# PCIe_x4.net
KiCad netlist of a schematic drawn in Altium Designer
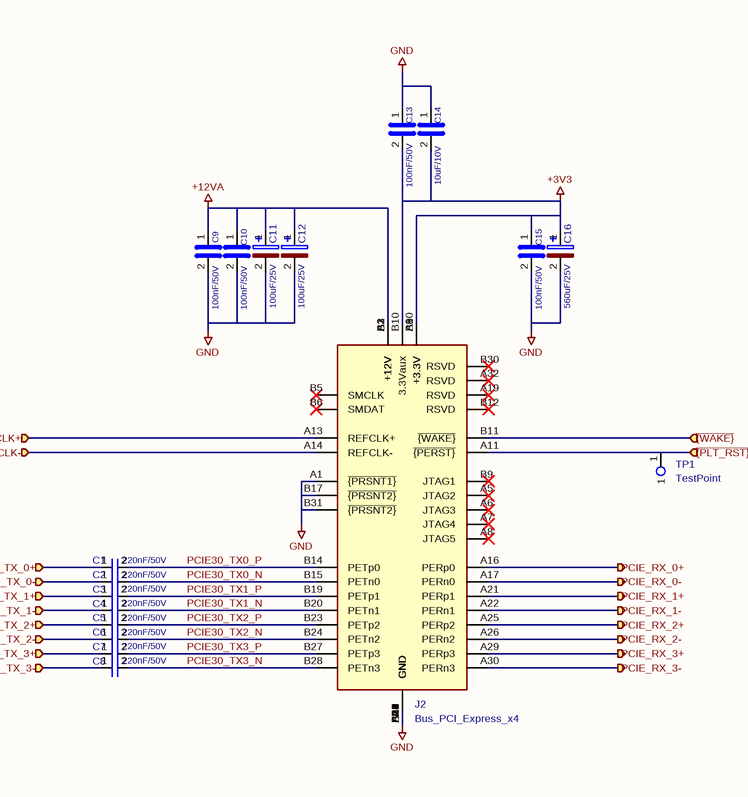
[diagram p0: PCIe x4.SchDoc]

(export (version "E")
  (design (tool "Eeschema 10.0.6"))
  (components
    (comp (ref "C1") (value "220nF/50V") (libsource (lib "Device") (part "C_Small")))
    (comp (ref "C2") (value "220nF/50V") (libsource (lib "Device") (part "C_Small")))
    (comp (ref "C3") (value "220nF/50V") (libsource (lib "Device") (part "C_Small")))
    (comp (ref "C4") (value "220nF/50V") (libsource (lib "Device") (part "C_Small")))
    (comp (ref "C5") (value "220nF/50V") (libsource (lib "Device") (part "C_Small")))
    (comp (ref "C6") (value "220nF/50V") (libsource (lib "Device") (part "C_Small")))
    (comp (ref "C7") (value "220nF/50V") (libsource (lib "Device") (part "C_Small")))
    (comp (ref "C8") (value "220nF/50V") (libsource (lib "Device") (part "C_Small")))
    (comp (ref "C9") (value "100nF/50V") (libsource (lib "Device") (part "C")))
    (comp (ref "C10") (value "100nF/50V") (libsource (lib "Device") (part "C")))
    (comp (ref "C11") (value "100uF/25V") (libsource (lib "Device") (part "C_Polarized")))
    (comp (ref "C12") (value "100uF/25V") (libsource (lib "Device") (part "C_Polarized")))
    (comp (ref "C13") (value "100nF/50V") (libsource (lib "Device") (part "C")))
    (comp (ref "C14") (value "10uF/10V") (libsource (lib "Device") (part "C")))
    (comp (ref "C15") (value "100nF/50V") (libsource (lib "Device") (part "C")))
    (comp (ref "C16") (value "560uF/25V") (libsource (lib "Device") (part "C_Polarized")))
    (comp (ref "J2") (value "Bus_PCI_Express_x4") (libsource (lib "Connector") (part "Bus_PCI_Express_x4")))
    (comp (ref "TP1") (value "TestPoint") (libsource (lib "Connector") (part "TestPoint")))
  )
  (nets
    (net (code "1") (name "+3V3") (class "Default")
      (node (ref "C13") (pin "2") (pinfunction "2_2") (pintype "passive"))
      (node (ref "C14") (pin "2") (pinfunction "2_2") (pintype "passive"))
      (node (ref "C15") (pin "1") (pinfunction "1_1") (pintype "passive"))
      (node (ref "C16") (pin "1") (pinfunction "1_1") (pintype "passive"))
      (node (ref "J2") (pin "A10") (pinfunction "+3.3V_A10") (pintype "passive"))
      (node (ref "J2") (pin "A9") (pinfunction "+3.3V_A9") (pintype "passive"))
      (node (ref "J2") (pin "B10") (pinfunction "3.3Vaux_B10") (pintype "passive"))
      (node (ref "J2") (pin "B8") (pinfunction "+3.3V_B8") (pintype "passive"))
    )
    (net (code "2") (name "+12VA") (class "Default")
      (node (ref "C10") (pin "1") (pinfunction "1_1") (pintype "passive"))
      (node (ref "C11") (pin "1") (pinfunction "1_1") (pintype "passive"))
      (node (ref "C12") (pin "1") (pinfunction "1_1") (pintype "passive"))
      (node (ref "C9") (pin "1") (pinfunction "1_1") (pintype "passive"))
      (node (ref "J2") (pin "A2") (pinfunction "+12V_A2") (pintype "passive"))
      (node (ref "J2") (pin "A3") (pinfunction "+12V_A3") (pintype "passive"))
      (node (ref "J2") (pin "B1") (pinfunction "+12V_B1") (pintype "passive"))
      (node (ref "J2") (pin "B2") (pinfunction "+12V_B2") (pintype "passive"))
      (node (ref "J2") (pin "B3") (pinfunction "+12V_B3") (pintype "passive"))
    )
    (net (code "3") (name "/PCIE30_TX0_N") (class "Default")
      (node (ref "C2") (pin "2") (pinfunction "2_2") (pintype "passive"))
      (node (ref "J2") (pin "B15") (pinfunction "PETn0_B15") (pintype "passive"))
    )
    (net (code "4") (name "/PCIE30_TX0_P") (class "Default")
      (node (ref "C1") (pin "2") (pinfunction "2_2") (pintype "passive"))
      (node (ref "J2") (pin "B14") (pinfunction "PETp0_B14") (pintype "passive"))
    )
    (net (code "5") (name "/PCIE30_TX1_N") (class "Default")
      (node (ref "C4") (pin "2") (pinfunction "2_2") (pintype "passive"))
      (node (ref "J2") (pin "B20") (pinfunction "PETn1_B20") (pintype "passive"))
    )
    (net (code "6") (name "/PCIE30_TX1_P") (class "Default")
      (node (ref "C3") (pin "2") (pinfunction "2_2") (pintype "passive"))
      (node (ref "J2") (pin "B19") (pinfunction "PETp1_B19") (pintype "passive"))
    )
    (net (code "7") (name "/PCIE30_TX2_N") (class "Default")
      (node (ref "C6") (pin "2") (pinfunction "2_2") (pintype "passive"))
      (node (ref "J2") (pin "B24") (pinfunction "PETn2_B24") (pintype "passive"))
    )
    (net (code "8") (name "/PCIE30_TX2_P") (class "Default")
      (node (ref "C5") (pin "2") (pinfunction "2_2") (pintype "passive"))
      (node (ref "J2") (pin "B23") (pinfunction "PETp2_B23") (pintype "passive"))
    )
    (net (code "9") (name "/PCIE30_TX3_N") (class "Default")
      (node (ref "C8") (pin "2") (pinfunction "2_2") (pintype "passive"))
      (node (ref "J2") (pin "B28") (pinfunction "PETn3_B28") (pintype "passive"))
    )
    (net (code "10") (name "/PCIE30_TX3_P") (class "Default")
      (node (ref "C7") (pin "2") (pinfunction "2_2") (pintype "passive"))
      (node (ref "J2") (pin "B27") (pinfunction "PETp3_B27") (pintype "passive"))
    )
    (net (code "11") (name "/PCIE_RX_0+") (class "Default")
      (node (ref "J2") (pin "A16") (pinfunction "PERp0_A16") (pintype "passive"))
    )
    (net (code "12") (name "/PCIE_RX_0-") (class "Default")
      (node (ref "J2") (pin "A17") (pinfunction "PERn0_A17") (pintype "passive"))
    )
    (net (code "13") (name "/PCIE_RX_1+") (class "Default")
      (node (ref "J2") (pin "A21") (pinfunction "PERp1_A21") (pintype "passive"))
    )
    (net (code "14") (name "/PCIE_RX_1-") (class "Default")
      (node (ref "J2") (pin "A22") (pinfunction "PERn1_A22") (pintype "passive"))
    )
    (net (code "15") (name "/PCIE_RX_2+") (class "Default")
      (node (ref "J2") (pin "A25") (pinfunction "PERp2_A25") (pintype "passive"))
    )
    (net (code "16") (name "/PCIE_RX_2-") (class "Default")
      (node (ref "J2") (pin "A26") (pinfunction "PERn2_A26") (pintype "passive"))
    )
    (net (code "17") (name "/PCIE_RX_3+") (class "Default")
      (node (ref "J2") (pin "A29") (pinfunction "PERp3_A29") (pintype "passive"))
    )
    (net (code "18") (name "/PCIE_RX_3-") (class "Default")
      (node (ref "J2") (pin "A30") (pinfunction "PERn3_A30") (pintype "passive"))
    )
    (net (code "19") (name "/PCIE_TX_0+") (class "Default")
      (node (ref "C1") (pin "1") (pinfunction "1_1") (pintype "passive"))
    )
    (net (code "20") (name "/PCIE_TX_0-") (class "Default")
      (node (ref "C2") (pin "1") (pinfunction "1_1") (pintype "passive"))
    )
    (net (code "21") (name "/PCIE_TX_1+") (class "Default")
      (node (ref "C3") (pin "1") (pinfunction "1_1") (pintype "passive"))
    )
    (net (code "22") (name "/PCIE_TX_1-") (class "Default")
      (node (ref "C4") (pin "1") (pinfunction "1_1") (pintype "passive"))
    )
    (net (code "23") (name "/PCIE_TX_2+") (class "Default")
      (node (ref "C5") (pin "1") (pinfunction "1_1") (pintype "passive"))
    )
    (net (code "24") (name "/PCIE_TX_2-") (class "Default")
      (node (ref "C6") (pin "1") (pinfunction "1_1") (pintype "passive"))
    )
    (net (code "25") (name "/PCIE_TX_3+") (class "Default")
      (node (ref "C7") (pin "1") (pinfunction "1_1") (pintype "passive"))
    )
    (net (code "26") (name "/PCIE_TX_3-") (class "Default")
      (node (ref "C8") (pin "1") (pinfunction "1_1") (pintype "passive"))
    )
    (net (code "27") (name "/REFCLK+") (class "Default")
      (node (ref "J2") (pin "A13") (pinfunction "REFCLK+_A13") (pintype "passive"))
    )
    (net (code "28") (name "/REFCLK-") (class "Default")
      (node (ref "J2") (pin "A14") (pinfunction "REFCLK-_A14") (pintype "passive"))
    )
    (net (code "29") (name "/~{{PLT_RST}}") (class "Default")
      (node (ref "J2") (pin "A11") (pinfunction "~{{PERST}}_A11") (pintype "passive"))
      (node (ref "TP1") (pin "1") (pinfunction "1_1") (pintype "passive"))
    )
    (net (code "30") (name "/~{{WAKE}}") (class "Default")
      (node (ref "J2") (pin "B11") (pinfunction "~{{WAKE}}_B11") (pintype "passive"))
    )
    (net (code "31") (name "GND") (class "Default")
      (node (ref "C10") (pin "2") (pinfunction "2_2") (pintype "passive"))
      (node (ref "C11") (pin "2") (pinfunction "2_2") (pintype "passive"))
      (node (ref "C12") (pin "2") (pinfunction "2_2") (pintype "passive"))
      (node (ref "C13") (pin "1") (pinfunction "1_1") (pintype "passive"))
      (node (ref "C14") (pin "1") (pinfunction "1_1") (pintype "passive"))
      (node (ref "C15") (pin "2") (pinfunction "2_2") (pintype "passive"))
      (node (ref "C16") (pin "2") (pinfunction "2_2") (pintype "passive"))
      (node (ref "C9") (pin "2") (pinfunction "2_2") (pintype "passive"))
      (node (ref "J2") (pin "A1") (pinfunction "~{{PRSNT1}}_A1") (pintype "passive"))
      (node (ref "J2") (pin "A12") (pinfunction "GND_A12") (pintype "passive"))
      (node (ref "J2") (pin "A15") (pinfunction "GND_A15") (pintype "passive"))
      (node (ref "J2") (pin "A18") (pinfunction "GND_A18") (pintype "passive"))
      (node (ref "J2") (pin "A20") (pinfunction "GND_A20") (pintype "passive"))
      (node (ref "J2") (pin "A23") (pinfunction "GND_A23") (pintype "passive"))
      (node (ref "J2") (pin "A24") (pinfunction "GND_A24") (pintype "passive"))
      (node (ref "J2") (pin "A27") (pinfunction "GND_A27") (pintype "passive"))
      (node (ref "J2") (pin "A28") (pinfunction "GND_A28") (pintype "passive"))
      (node (ref "J2") (pin "A31") (pinfunction "GND_A31") (pintype "passive"))
      (node (ref "J2") (pin "A4") (pinfunction "GND_A4") (pintype "passive"))
      (node (ref "J2") (pin "B13") (pinfunction "GND_B13") (pintype "passive"))
      (node (ref "J2") (pin "B16") (pinfunction "GND_B16") (pintype "passive"))
      (node (ref "J2") (pin "B17") (pinfunction "~{{PRSNT2}}_B17") (pintype "passive"))
      (node (ref "J2") (pin "B18") (pinfunction "GND_B18") (pintype "passive"))
      (node (ref "J2") (pin "B21") (pinfunction "GND_B21") (pintype "passive"))
      (node (ref "J2") (pin "B22") (pinfunction "GND_B22") (pintype "passive"))
      (node (ref "J2") (pin "B25") (pinfunction "GND_B25") (pintype "passive"))
      (node (ref "J2") (pin "B26") (pinfunction "GND_B26") (pintype "passive"))
      (node (ref "J2") (pin "B29") (pinfunction "GND_B29") (pintype "passive"))
      (node (ref "J2") (pin "B31") (pinfunction "~{{PRSNT2}}_B31") (pintype "passive"))
      (node (ref "J2") (pin "B32") (pinfunction "GND_B32") (pintype "passive"))
      (node (ref "J2") (pin "B4") (pinfunction "GND_B4") (pintype "passive"))
      (node (ref "J2") (pin "B7") (pinfunction "GND_B7") (pintype "passive"))
    )
    (net (code "32") (name "unconnected-(J2-JTAG1-PadB9)") (class "Default")
      (node (ref "J2") (pin "B9") (pinfunction "JTAG1_B9") (pintype "passive+no_connect"))
    )
    (net (code "33") (name "unconnected-(J2-JTAG2-PadA5)") (class "Default")
      (node (ref "J2") (pin "A5") (pinfunction "JTAG2_A5") (pintype "passive+no_connect"))
    )
    (net (code "34") (name "unconnected-(J2-JTAG3-PadA6)") (class "Default")
      (node (ref "J2") (pin "A6") (pinfunction "JTAG3_A6") (pintype "passive+no_connect"))
    )
    (net (code "35") (name "unconnected-(J2-JTAG4-PadA7)") (class "Default")
      (node (ref "J2") (pin "A7") (pinfunction "JTAG4_A7") (pintype "passive+no_connect"))
    )
    (net (code "36") (name "unconnected-(J2-JTAG5-PadA8)") (class "Default")
      (node (ref "J2") (pin "A8") (pinfunction "JTAG5_A8") (pintype "passive+no_connect"))
    )
    (net (code "37") (name "unconnected-(J2-RSVD-PadA19)") (class "Default")
      (node (ref "J2") (pin "A19") (pinfunction "RSVD_A19") (pintype "passive+no_connect"))
    )
    (net (code "38") (name "unconnected-(J2-RSVD-PadA32)") (class "Default")
      (node (ref "J2") (pin "A32") (pinfunction "RSVD_A32") (pintype "passive+no_connect"))
    )
    (net (code "39") (name "unconnected-(J2-RSVD-PadB12)") (class "Default")
      (node (ref "J2") (pin "B12") (pinfunction "RSVD_B12") (pintype "passive+no_connect"))
    )
    (net (code "40") (name "unconnected-(J2-RSVD-PadB30)") (class "Default")
      (node (ref "J2") (pin "B30") (pinfunction "RSVD_B30") (pintype "passive+no_connect"))
    )
    (net (code "41") (name "unconnected-(J2-SMCLK-PadB5)") (class "Default")
      (node (ref "J2") (pin "B5") (pinfunction "SMCLK_B5") (pintype "passive+no_connect"))
    )
    (net (code "42") (name "unconnected-(J2-SMDAT-PadB6)") (class "Default")
      (node (ref "J2") (pin "B6") (pinfunction "SMDAT_B6") (pintype "passive+no_connect"))
    )
  )
)
